# CV_Control.net
KiCad netlist of a schematic drawn in Altium Designer
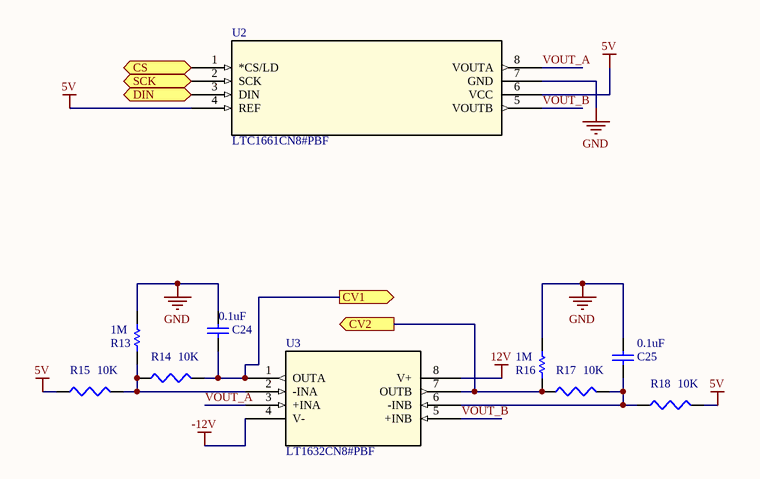
[diagram p0: CV_Control.SchDoc]

(export (version "E")
  (design (tool "Eeschema 10.0.6"))
  (components
    (comp (ref "C24")
      (value "0.1uF")
      (footprint "RAD-0.3")
      (description "Capacitor")
      (fields (field (name "Comment") "Cap") (field (name "PUBLISHER") "Altium Limited"))
      (libsource (lib "Miscellaneous Devices") (part "Cap"))
    )
    (comp (ref "C25")
      (value "0.1uF")
      (footprint "RAD-0.3")
      (description "Capacitor")
      (fields (field (name "Comment") "Cap") (field (name "PUBLISHER") "Altium Limited"))
      (libsource (lib "Miscellaneous Devices") (part "Cap"))
    )
    (comp (ref "R13")
      (value "1M")
      (footprint "AXIAL-0.3")
      (description "Resistor")
      (fields (field (name "Comment") "Res1") (field (name "PUBLISHER") "Altium Limited"))
      (libsource (lib "Miscellaneous Devices") (part "Res1"))
    )
    (comp (ref "R14")
      (value "10K")
      (footprint "J1-0603")
      (description "Resistor")
      (fields (field (name "Comment") "Res3") (field (name "PUBLISHER") "Altium Limited"))
      (libsource (lib "Miscellaneous Devices") (part "Res3"))
    )
    (comp (ref "R15")
      (value "10K")
      (footprint "J1-0603")
      (description "Resistor")
      (fields (field (name "Comment") "Res3") (field (name "PUBLISHER") "Altium Limited"))
      (libsource (lib "Miscellaneous Devices") (part "Res3"))
    )
    (comp (ref "R16")
      (value "1M")
      (footprint "AXIAL-0.3")
      (description "Resistor")
      (fields (field (name "Comment") "Res1") (field (name "PUBLISHER") "Altium Limited"))
      (libsource (lib "Miscellaneous Devices") (part "Res1"))
    )
    (comp (ref "R17")
      (value "10K")
      (footprint "J1-0603")
      (description "Resistor")
      (fields (field (name "Comment") "Res3") (field (name "PUBLISHER") "Altium Limited"))
      (libsource (lib "Miscellaneous Devices") (part "Res3"))
    )
    (comp (ref "R18")
      (value "10K")
      (footprint "J1-0603")
      (description "Resistor")
      (fields (field (name "Comment") "Res3") (field (name "PUBLISHER") "Altium Limited"))
      (libsource (lib "Miscellaneous Devices") (part "Res3"))
    )
    (comp (ref "U2")
      (value "LTC1661CN8#PBF")
      (footprint "PDIP-8_N")
      (description "Imported")
      (libsource (lib "lt1661") (part "LTC1661CN8#PBF"))
    )
    (comp (ref "U3")
      (value "LT1632CN8#PBF")
      (footprint "PDIP-8_N")
      (description "Imported")
      (fields
        (field (name "DIGIKEYPARTNUMBER") "LT1632CN8-ND")
        (field (name "COPYRIGHT") "Copyright (C) 2015 Accelerated Designs. All rights reserved")
      )
      (libsource (lib "lt1632") (part "LT1632CN8#PBF"))
    )
  )
  (nets
    (net (code "1") (name "-12V") (class "Default")
      (node (ref "U3") (pin "4") (pinfunction "V-_4") (pintype "power_in"))
    )
    (net (code "2") (name "/CS") (class "Default")
      (node (ref "U2") (pin "1") (pinfunction "*CS/LD_1") (pintype "input"))
    )
    (net (code "3") (name "/CV1") (class "Default")
      (node (ref "C24") (pin "1") (pinfunction "1_1") (pintype "passive"))
      (node (ref "R14") (pin "2") (pinfunction "2_2") (pintype "passive"))
      (node (ref "U3") (pin "1") (pinfunction "OUTA_1") (pintype "output"))
    )
    (net (code "4") (name "/CV2") (class "Default")
      (node (ref "R16") (pin "1") (pinfunction "1_1") (pintype "passive"))
      (node (ref "R17") (pin "1") (pinfunction "1_1") (pintype "passive"))
      (node (ref "U3") (pin "7") (pinfunction "OUTB_7") (pintype "output"))
    )
    (net (code "5") (name "/DIN") (class "Default")
      (node (ref "U2") (pin "3") (pinfunction "DIN_3") (pintype "input"))
    )
    (net (code "6") (name "/SCK") (class "Default")
      (node (ref "U2") (pin "2") (pinfunction "SCK_2") (pintype "input"))
    )
    (net (code "7") (name "/VOUT_A") (class "Default")
      (node (ref "U2") (pin "8") (pinfunction "VOUTA_8") (pintype "output"))
      (node (ref "U3") (pin "3") (pinfunction "+INA_3") (pintype "input"))
    )
    (net (code "8") (name "/VOUT_B") (class "Default")
      (node (ref "U2") (pin "5") (pinfunction "VOUTB_5") (pintype "output"))
      (node (ref "U3") (pin "5") (pinfunction "+INB_5") (pintype "input"))
    )
    (net (code "9") (name "5V") (class "Default")
      (node (ref "R15") (pin "1") (pinfunction "1_1") (pintype "passive"))
      (node (ref "R18") (pin "2") (pinfunction "2_2") (pintype "passive"))
      (node (ref "U2") (pin "4") (pinfunction "REF_4") (pintype "input"))
      (node (ref "U2") (pin "6") (pinfunction "VCC_6") (pintype "power_in"))
    )
    (net (code "10") (name "12V") (class "Default")
      (node (ref "U3") (pin "8") (pinfunction "V+_8") (pintype "power_in"))
    )
    (net (code "11") (name "GND") (class "Default")
      (node (ref "C24") (pin "2") (pinfunction "2_2") (pintype "passive"))
      (node (ref "C25") (pin "2") (pinfunction "2_2") (pintype "passive"))
      (node (ref "R13") (pin "2") (pinfunction "2_2") (pintype "passive"))
      (node (ref "R16") (pin "2") (pinfunction "2_2") (pintype "passive"))
      (node (ref "U2") (pin "7") (pinfunction "GND_7") (pintype "power_in"))
    )
    (net (code "12") (name "Net-(U3--INA)") (class "Default")
      (node (ref "R13") (pin "1") (pinfunction "1_1") (pintype "passive"))
      (node (ref "R14") (pin "1") (pinfunction "1_1") (pintype "passive"))
      (node (ref "R15") (pin "2") (pinfunction "2_2") (pintype "passive"))
      (node (ref "U3") (pin "2") (pinfunction "-INA_2") (pintype "input"))
    )
    (net (code "13") (name "Net-(U3--INB)") (class "Default")
      (node (ref "C25") (pin "1") (pinfunction "1_1") (pintype "passive"))
      (node (ref "R17") (pin "2") (pinfunction "2_2") (pintype "passive"))
      (node (ref "R18") (pin "1") (pinfunction "1_1") (pintype "passive"))
      (node (ref "U3") (pin "6") (pinfunction "-INB_6") (pintype "input"))
    )
  )
)
